# MAIN.net
KiCad netlist of a schematic drawn in Altium Designer
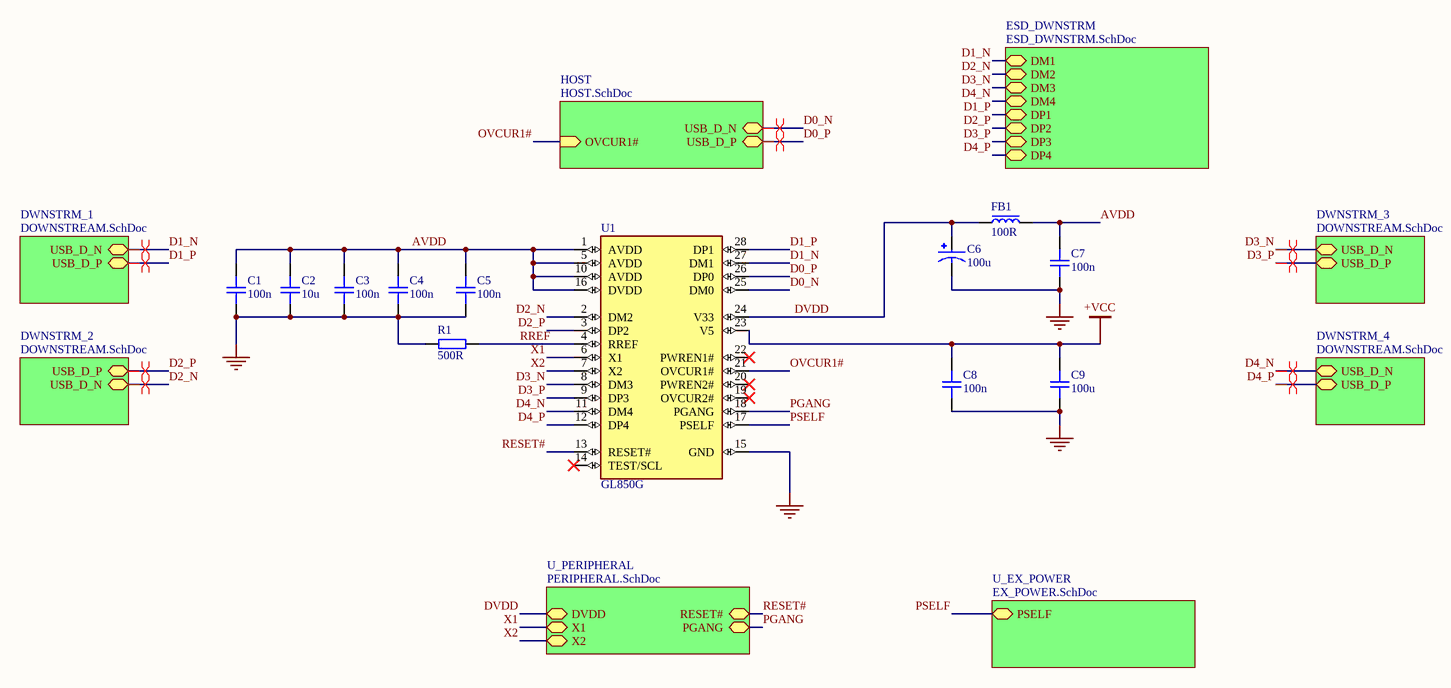
[diagram p0: MAIN.SchDoc]

(export (version "E")
  (design (tool "Eeschema 10.0.6"))
  (components
    (comp (ref "C1")
      (value "100n")
      (footprint "CAP_0805")
      (description "Capacitor SMD 0805")
      (libsource (lib "Schematic-Lib-PhilsLab") (part "CAP_0805"))
    )
    (comp (ref "C2")
      (value "10u")
      (footprint "CAP_0805")
      (description "Capacitor SMD 0805")
      (libsource (lib "Schematic-Lib-PhilsLab") (part "CAP_0805"))
    )
    (comp (ref "C3")
      (value "100n")
      (footprint "CAP_0805")
      (description "Capacitor SMD 0805")
      (libsource (lib "Schematic-Lib-PhilsLab") (part "CAP_0805"))
    )
    (comp (ref "C4")
      (value "100n")
      (footprint "CAP_0805")
      (description "Capacitor SMD 0805")
      (libsource (lib "Schematic-Lib-PhilsLab") (part "CAP_0805"))
    )
    (comp (ref "C5")
      (value "100n")
      (footprint "CAP_0805")
      (description "Capacitor SMD 0805")
      (libsource (lib "Schematic-Lib-PhilsLab") (part "CAP_0805"))
    )
    (comp (ref "C6")
      (value "100u")
      (footprint "CAP_EEEHA0J101WR")
      (fields (field (name "MF") "Panasonic Electronic") (field (name "MP") "EEE-HA0J101WR"))
      (libsource (lib "Schematic-Lib-PhilsLab") (part "EEEHA0J101WR"))
    )
    (comp (ref "C7")
      (value "100n")
      (footprint "CAP_0805")
      (description "Capacitor SMD 0805")
      (libsource (lib "Schematic-Lib-PhilsLab") (part "CAP_0805"))
    )
    (comp (ref "C8")
      (value "100n")
      (footprint "CAP_0805")
      (description "Capacitor SMD 0805")
      (libsource (lib "Schematic-Lib-PhilsLab") (part "CAP_0805"))
    )
    (comp (ref "C9")
      (value "100u")
      (footprint "CAP_0805")
      (description "Capacitor SMD 0805")
      (libsource (lib "Schematic-Lib-PhilsLab") (part "CAP_0805"))
    )
    (comp (ref "FB1")
      (value "100R")
      (footprint "FB_0603")
      (description "Ferrite Bead SMD 0603")
      (libsource (lib "Schematic-Lib-PhilsLab") (part "FB_0603"))
    )
    (comp (ref "R1")
      (value "500R")
      (footprint "RES_0603")
      (description "Resistor SMD 0603")
      (libsource (lib "Schematic-Lib-PhilsLab") (part "RES_0603"))
    )
    (comp (ref "U1")
      (value "GL850G")
      (footprint "SSOP28")
      (description "Programmable Logic IC Development Tools")
      (fields (field (name "MANUFACTURER") "Vishay Intertechnology"))
      (libsource (lib "Schematic-Lib-PhilsLab") (part "GL850G"))
    )
  )
  (nets
    (net (code "1") (name "+VCC") (class "Default")
      (node (ref "C8") (pin "2") (pinfunction "2_2") (pintype "passive"))
      (node (ref "C9") (pin "2") (pinfunction "2_2") (pintype "passive"))
      (node (ref "U1") (pin "23") (pinfunction "V5_23") (pintype "bidirectional"))
    )
    (net (code "2") (name "/AVDD") (class "Default")
      (node (ref "C1") (pin "2") (pinfunction "2_2") (pintype "passive"))
      (node (ref "C2") (pin "2") (pinfunction "2_2") (pintype "passive"))
      (node (ref "C3") (pin "1") (pinfunction "1_1") (pintype "passive"))
      (node (ref "C4") (pin "2") (pinfunction "2_2") (pintype "passive"))
      (node (ref "C5") (pin "2") (pinfunction "2_2") (pintype "passive"))
      (node (ref "C7") (pin "2") (pinfunction "2_2") (pintype "passive"))
      (node (ref "FB1") (pin "2") (pinfunction "2_2") (pintype "passive"))
      (node (ref "U1") (pin "1") (pinfunction "AVDD_1") (pintype "bidirectional"))
      (node (ref "U1") (pin "10") (pinfunction "AVDD_10") (pintype "bidirectional"))
      (node (ref "U1") (pin "16") (pinfunction "DVDD_16") (pintype "bidirectional"))
      (node (ref "U1") (pin "5") (pinfunction "AVDD_5") (pintype "bidirectional"))
    )
    (net (code "3") (name "/D0_N") (class "Default")
      (node (ref "U1") (pin "25") (pinfunction "DM0_25") (pintype "bidirectional"))
    )
    (net (code "4") (name "/D0_P") (class "Default")
      (node (ref "U1") (pin "26") (pinfunction "DP0_26") (pintype "bidirectional"))
    )
    (net (code "5") (name "/D1_N") (class "Default")
      (node (ref "U1") (pin "27") (pinfunction "DM1_27") (pintype "bidirectional"))
    )
    (net (code "6") (name "/D1_P") (class "Default")
      (node (ref "U1") (pin "28") (pinfunction "DP1_28") (pintype "bidirectional"))
    )
    (net (code "7") (name "/D2_N") (class "Default")
      (node (ref "U1") (pin "2") (pinfunction "DM2_2") (pintype "bidirectional"))
    )
    (net (code "8") (name "/D2_P") (class "Default")
      (node (ref "U1") (pin "3") (pinfunction "DP2_3") (pintype "bidirectional"))
    )
    (net (code "9") (name "/D3_N") (class "Default")
      (node (ref "U1") (pin "8") (pinfunction "DM3_8") (pintype "bidirectional"))
    )
    (net (code "10") (name "/D3_P") (class "Default")
      (node (ref "U1") (pin "9") (pinfunction "DP3_9") (pintype "bidirectional"))
    )
    (net (code "11") (name "/D4_N") (class "Default")
      (node (ref "U1") (pin "11") (pinfunction "DM4_11") (pintype "bidirectional"))
    )
    (net (code "12") (name "/D4_P") (class "Default")
      (node (ref "U1") (pin "12") (pinfunction "DP4_12") (pintype "bidirectional"))
    )
    (net (code "13") (name "/DVDD") (class "Default")
      (node (ref "C6") (pin "1") (pinfunction "1_1") (pintype "passive"))
      (node (ref "FB1") (pin "1") (pinfunction "1_1") (pintype "passive"))
      (node (ref "U1") (pin "24") (pinfunction "V33_24") (pintype "bidirectional"))
    )
    (net (code "14") (name "/OVCUR1#") (class "Default")
      (node (ref "U1") (pin "21") (pinfunction "OVCUR1#_21") (pintype "bidirectional"))
    )
    (net (code "15") (name "/PGANG") (class "Default")
      (node (ref "U1") (pin "18") (pinfunction "PGANG_18") (pintype "bidirectional"))
    )
    (net (code "16") (name "/PSELF") (class "Default")
      (node (ref "U1") (pin "17") (pinfunction "PSELF_17") (pintype "bidirectional"))
    )
    (net (code "17") (name "/RESET#") (class "Default")
      (node (ref "U1") (pin "13") (pinfunction "RESET#_13") (pintype "bidirectional"))
    )
    (net (code "18") (name "/RREF") (class "Default")
      (node (ref "R1") (pin "2") (pinfunction "2_2") (pintype "passive"))
      (node (ref "U1") (pin "4") (pinfunction "RREF_4") (pintype "bidirectional"))
    )
    (net (code "19") (name "/X1") (class "Default")
      (node (ref "U1") (pin "6") (pinfunction "X1_6") (pintype "bidirectional"))
    )
    (net (code "20") (name "/X2") (class "Default")
      (node (ref "U1") (pin "7") (pinfunction "X2_7") (pintype "bidirectional"))
    )
    (net (code "21") (name "GND") (class "Default")
      (node (ref "C1") (pin "1") (pinfunction "1_1") (pintype "passive"))
      (node (ref "C2") (pin "1") (pinfunction "1_1") (pintype "passive"))
      (node (ref "C3") (pin "2") (pinfunction "2_2") (pintype "passive"))
      (node (ref "C4") (pin "1") (pinfunction "1_1") (pintype "passive"))
      (node (ref "C5") (pin "1") (pinfunction "1_1") (pintype "passive"))
      (node (ref "C6") (pin "2") (pinfunction "2_2") (pintype "passive"))
      (node (ref "C7") (pin "1") (pinfunction "1_1") (pintype "passive"))
      (node (ref "C8") (pin "1") (pinfunction "1_1") (pintype "passive"))
      (node (ref "C9") (pin "1") (pinfunction "1_1") (pintype "passive"))
      (node (ref "R1") (pin "1") (pinfunction "1_1") (pintype "passive"))
      (node (ref "U1") (pin "15") (pinfunction "GND_15") (pintype "bidirectional"))
    )
    (net (code "22") (name "unconnected-(U1-OVCUR2#-Pad19)") (class "Default")
      (node (ref "U1") (pin "19") (pinfunction "OVCUR2#_19") (pintype "bidirectional+no_connect"))
    )
    (net (code "23") (name "unconnected-(U1-PWREN1#-Pad22)") (class "Default")
      (node (ref "U1") (pin "22") (pinfunction "PWREN1#_22") (pintype "bidirectional+no_connect"))
    )
    (net (code "24") (name "unconnected-(U1-PWREN2#-Pad20)") (class "Default")
      (node (ref "U1") (pin "20") (pinfunction "PWREN2#_20") (pintype "bidirectional+no_connect"))
    )
    (net (code "25") (name "unconnected-(U1-TEST{slash}SCL-Pad14)") (class "Default")
      (node (ref "U1") (pin "14") (pinfunction "TEST/SCL_14") (pintype "bidirectional+no_connect"))
    )
  )
)
